# Accumulator_Indicator.net
KiCad netlist of a schematic drawn in Altium Designer
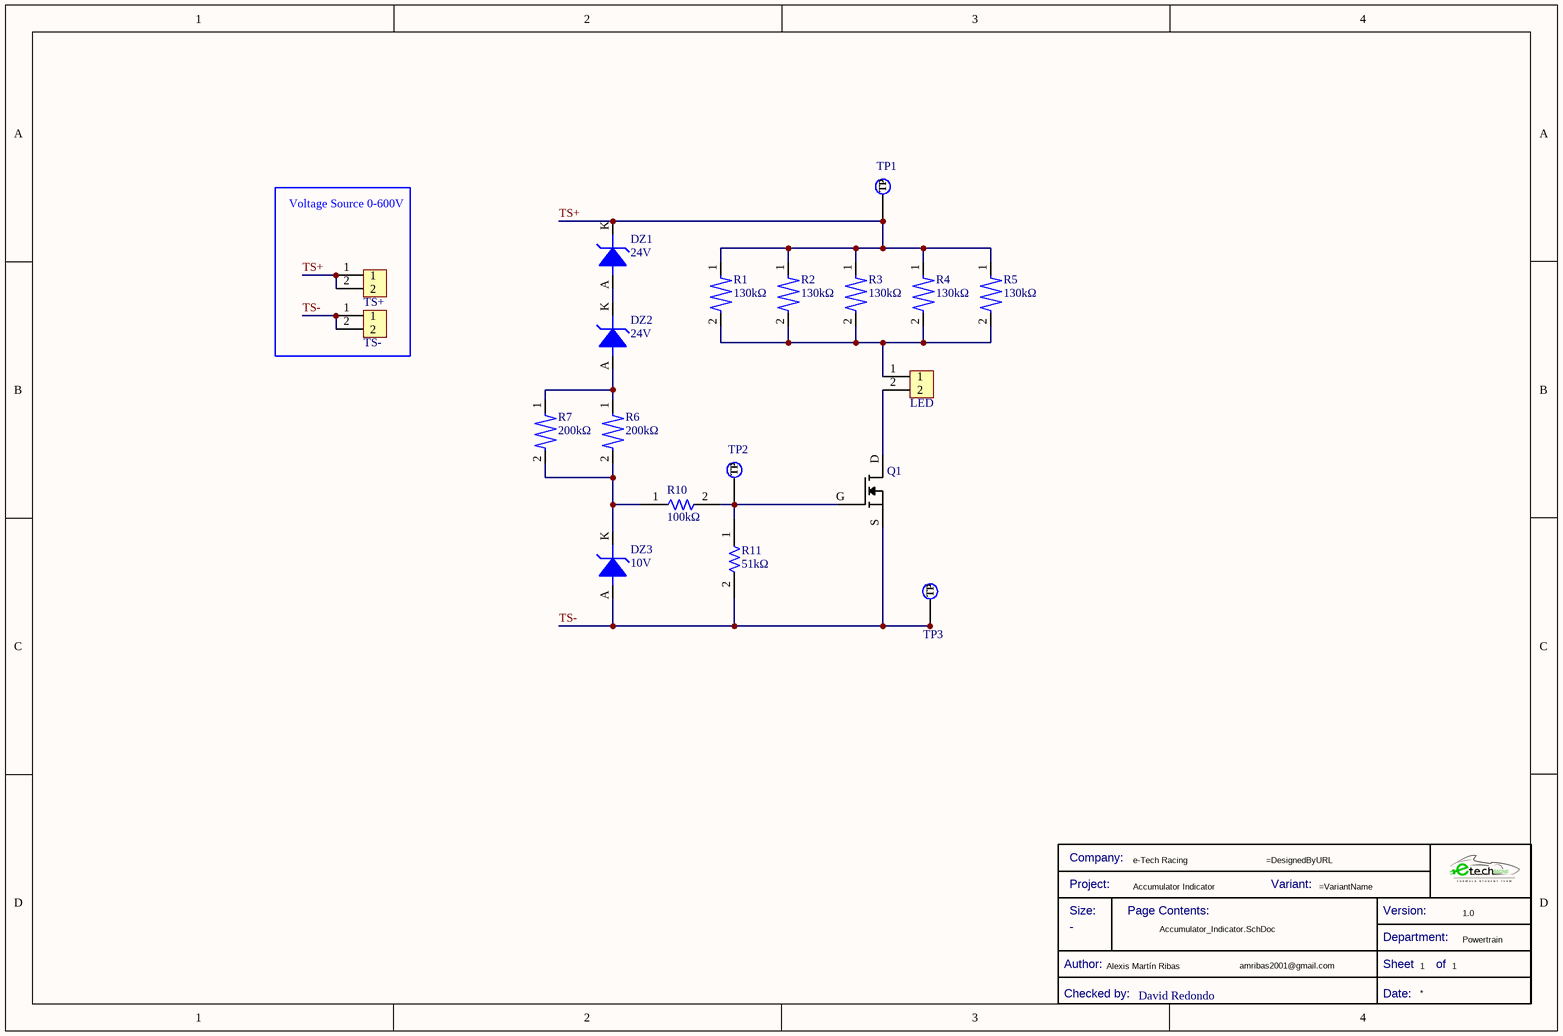
[diagram p0: Accumulator_Indicator.SchDoc]

(export (version "E")
  (design (tool "Eeschema 10.0.6"))
  (components
    (comp (ref "*")
      (value "Title Block_template")
      (description "Standard Title Block")
      (fields
        (field (name "SIZE") "-")
        (field (name ".CREATOR") "GP")
        (field (name ".PCBCHECK") "GP")
        (field (name ".SCHCHECK") "GP")
      )
      (libsource (lib "e-Tech_Racing") (part "Title Block_template"))
    )
    (comp (ref "DZ1")
      (value "24V")
      (footprint "DZ_24V_STD")
      (description "BZX55C24")
      (libsource (lib "AM_Schlib") (part "DZ_24V_STD"))
    )
    (comp (ref "DZ2")
      (value "24V")
      (footprint "DZ_24V_STD")
      (description "BZX55C24")
      (libsource (lib "AM_Schlib") (part "DZ_24V_STD"))
    )
    (comp (ref "DZ3")
      (value "10V")
      (footprint "DZ_24V_BZT52H-A10-Q")
      (libsource (lib "AM_Schlib") (part "DZ_24V_BZT52H-A10-Q"))
    )
    (comp (ref "LED")
      (value "436500215")
      (footprint "J_MicroFit_2x1")
      (description "Header 1 Row Vertical Polarizing Peg 2 Pin SMT/Glow Wire Compatible Tin Plate")
      (libsource (lib "Electromechanical") (part "J_MicroFit_2x1"))
    )
    (comp (ref "Q1")
      (value "D2PAK type-A")
      (footprint "MOSFET-N-D2PAK")
      (description "STB36N60M6")
      (libsource (lib "AM_Schlib") (part "MOSFET-N-D2PAK"))
    )
    (comp (ref "R1")
      (value "130kΩ")
      (footprint "R130K_3W413")
      (libsource (lib "AM_Schlib") (part "R130K_3W413"))
    )
    (comp (ref "R2")
      (value "130kΩ")
      (footprint "R130K_3W413")
      (libsource (lib "AM_Schlib") (part "R130K_3W413"))
    )
    (comp (ref "R3")
      (value "130kΩ")
      (footprint "R130K_3W413")
      (libsource (lib "AM_Schlib") (part "R130K_3W413"))
    )
    (comp (ref "R4")
      (value "130kΩ")
      (footprint "R130K_3W413")
      (libsource (lib "AM_Schlib") (part "R130K_3W413"))
    )
    (comp (ref "R5")
      (value "130kΩ")
      (footprint "R130K_3W413")
      (libsource (lib "AM_Schlib") (part "R130K_3W413"))
    )
    (comp (ref "R6") (value "200kΩ") (footprint "R200K_2W") (libsource (lib "AM_Schlib") (part "R200K_2W")))
    (comp (ref "R7") (value "200kΩ") (footprint "R200K_2W") (libsource (lib "AM_Schlib") (part "R200K_2W")))
    (comp (ref "R10")
      (value "CRG1206F100R")
      (footprint "R1206FTK-W")
      (description "Res Thick Film 1206 100 Ohm 1% 0.25W(1/4W) ±200ppm/C Pad SMD T/R")
      (fields
        (field (name "MANUFACTURER") "TE Connectivity")
        (field (name "TOLERANCE") "1%")
        (field (name "RESISTANCE") "100kΩ")
        (field (name ".CREATOR") "AC")
      )
      (libsource (lib "Passives") (part "R100-1206FTK"))
    )
    (comp (ref "R11")
      (value "CRCW120610K0FKEA")
      (footprint "R1206FTK-W")
      (description "Res Thick Film 1206 51K Ohm 1% 1/4W ±100ppm/°C Molded SMD SMD Punched Carrier T/R")
      (fields
        (field (name "MANUFACTURER") "Panasonic")
        (field (name "MANUFACTURER PART NUMBER") "ERJ-S08F5102V")
        (field (name "RESISTANCE") "51kΩ")
        (field (name ".CREATOR") "DO")
      )
      (libsource (lib "Passives") (part "R51k-1206FTK"))
    )
    (comp (ref "TP1")
      (value "TestPoint")
      (footprint "TestPoint")
      (description "Test Point 1x1 mm")
      (fields (field (name ".CREATOR") "GP") (field (name ".PCBCHECK") "GP") (field (name ".SCHCHECK") "GP"))
      (libsource (lib "e-Tech_Racing") (part "TestPoint"))
    )
    (comp (ref "TP2")
      (value "TestPoint")
      (footprint "TestPoint")
      (description "Test Point 1x1 mm")
      (fields (field (name ".CREATOR") "GP") (field (name ".PCBCHECK") "GP") (field (name ".SCHCHECK") "GP"))
      (libsource (lib "e-Tech_Racing") (part "TestPoint"))
    )
    (comp (ref "TP3")
      (value "TestPoint")
      (footprint "TestPoint")
      (description "Test Point 1x1 mm")
      (fields (field (name ".CREATOR") "GP") (field (name ".PCBCHECK") "GP") (field (name ".SCHCHECK") "GP"))
      (libsource (lib "e-Tech_Racing") (part "TestPoint"))
    )
    (comp (ref "TS+")
      (value "436500215")
      (footprint "J_MicroFit_2x1")
      (description "Header 1 Row Vertical Polarizing Peg 2 Pin SMT/Glow Wire Compatible Tin Plate")
      (libsource (lib "Electromechanical") (part "J_MicroFit_2x1"))
    )
    (comp (ref "TS-")
      (value "436500215")
      (footprint "J_MicroFit_2x1")
      (description "Header 1 Row Vertical Polarizing Peg 2 Pin SMT/Glow Wire Compatible Tin Plate")
      (libsource (lib "Electromechanical") (part "J_MicroFit_2x1"))
    )
  )
  (nets
    (net (code "1") (name "/TS+") (class "Default")
      (node (ref "DZ1") (pin "K") (pinfunction "K_K") (pintype "passive"))
      (node (ref "R1") (pin "1") (pinfunction "1_1") (pintype "passive"))
      (node (ref "R2") (pin "1") (pinfunction "1_1") (pintype "passive"))
      (node (ref "R3") (pin "1") (pinfunction "1_1") (pintype "passive"))
      (node (ref "R4") (pin "1") (pinfunction "1_1") (pintype "passive"))
      (node (ref "R5") (pin "1") (pinfunction "1_1") (pintype "passive"))
      (node (ref "TP1") (pin "1") (pinfunction "TP_1") (pintype "passive"))
      (node (ref "TS+") (pin "1") (pinfunction "1_1") (pintype "passive"))
      (node (ref "TS+") (pin "2") (pinfunction "2_2") (pintype "passive"))
    )
    (net (code "2") (name "/TS-") (class "Default")
      (node (ref "DZ3") (pin "A") (pinfunction "A_A") (pintype "passive"))
      (node (ref "Q1") (pin "S") (pinfunction "S_S") (pintype "passive"))
      (node (ref "R11") (pin "2") (pinfunction "2_2") (pintype "passive"))
      (node (ref "TP3") (pin "1") (pinfunction "TP_1") (pintype "passive"))
      (node (ref "TS-") (pin "1") (pinfunction "1_1") (pintype "passive"))
      (node (ref "TS-") (pin "2") (pinfunction "2_2") (pintype "passive"))
    )
    (net (code "3") (name "Net-(DZ1-PadA)") (class "Default")
      (node (ref "DZ1") (pin "A") (pinfunction "A_A") (pintype "passive"))
      (node (ref "DZ2") (pin "K") (pinfunction "K_K") (pintype "passive"))
    )
    (net (code "4") (name "Net-(DZ2-PadA)") (class "Default")
      (node (ref "DZ2") (pin "A") (pinfunction "A_A") (pintype "passive"))
      (node (ref "R6") (pin "1") (pinfunction "1_1") (pintype "passive"))
      (node (ref "R7") (pin "1") (pinfunction "1_1") (pintype "passive"))
    )
    (net (code "5") (name "Net-(DZ3-PadK)") (class "Default")
      (node (ref "DZ3") (pin "K") (pinfunction "K_K") (pintype "passive"))
      (node (ref "R10") (pin "1") (pinfunction "1_1") (pintype "passive"))
      (node (ref "R6") (pin "2") (pinfunction "2_2") (pintype "passive"))
      (node (ref "R7") (pin "2") (pinfunction "2_2") (pintype "passive"))
    )
    (net (code "6") (name "Net-(LED-Pad1)") (class "Default")
      (node (ref "LED") (pin "1") (pinfunction "1_1") (pintype "passive"))
      (node (ref "R1") (pin "2") (pinfunction "2_2") (pintype "passive"))
      (node (ref "R2") (pin "2") (pinfunction "2_2") (pintype "passive"))
      (node (ref "R3") (pin "2") (pinfunction "2_2") (pintype "passive"))
      (node (ref "R4") (pin "2") (pinfunction "2_2") (pintype "passive"))
      (node (ref "R5") (pin "2") (pinfunction "2_2") (pintype "passive"))
    )
    (net (code "7") (name "Net-(LED-Pad2)") (class "Default")
      (node (ref "LED") (pin "2") (pinfunction "2_2") (pintype "passive"))
      (node (ref "Q1") (pin "D") (pinfunction "D_D") (pintype "passive"))
    )
    (net (code "8") (name "Net-(TP2-TP)") (class "Default")
      (node (ref "Q1") (pin "G") (pinfunction "G_G") (pintype "passive"))
      (node (ref "R10") (pin "2") (pinfunction "2_2") (pintype "passive"))
      (node (ref "R11") (pin "1") (pinfunction "1_1") (pintype "passive"))
      (node (ref "TP2") (pin "1") (pinfunction "TP_1") (pintype "passive"))
    )
  )
)
